# Peripherals.net
KiCad netlist of a schematic drawn in Altium Designer
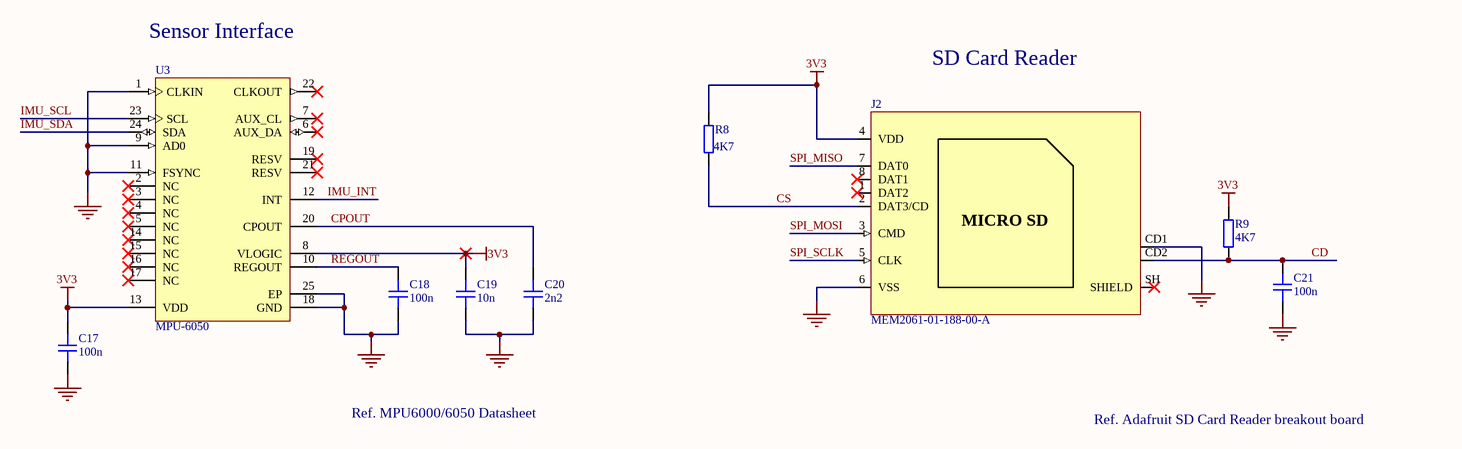
[diagram p0: Peripherals.SchDoc]

(export (version "E")
  (design (tool "Eeschema 10.0.6"))
  (components
    (comp (ref "C17")
      (value "100n")
      (footprint "CAP_0402")
      (description "Capacitor SMD 0402")
      (libsource (lib "Schematic-Lib-PhilsLab") (part "CAP_0402"))
    )
    (comp (ref "C18")
      (value "100n")
      (footprint "CAP_0402")
      (description "Capacitor SMD 0402")
      (libsource (lib "Schematic-Lib-PhilsLab") (part "CAP_0402"))
    )
    (comp (ref "C19")
      (value "10n")
      (footprint "CAP_0402")
      (description "Capacitor SMD 0402")
      (libsource (lib "Schematic-Lib-PhilsLab") (part "CAP_0402"))
    )
    (comp (ref "C20")
      (value "2n2")
      (footprint "CAP_0402")
      (description "Capacitor SMD 0402")
      (libsource (lib "Schematic-Lib-PhilsLab") (part "CAP_0402"))
    )
    (comp (ref "C21")
      (value "100n")
      (footprint "CAP_0402")
      (description "Capacitor SMD 0402")
      (libsource (lib "Schematic-Lib-PhilsLab") (part "CAP_0402"))
    )
    (comp (ref "J2")
      (value "MEM2061-01-188-00-A")
      (footprint "MEM2061-01-188-00-A")
      (description "Micro SD Card Holder Push-Push SMD")
      (fields (field (name "MANUFACTURER") "GCT"))
      (libsource (lib "Schematic-Lib-PhilsLab") (part "MEM2061-01-188-00-A"))
    )
    (comp (ref "R8")
      (value "4K7")
      (footprint "RES_0402")
      (description "Resistor SMD 0402")
      (libsource (lib "Schematic-Lib-PhilsLab") (part "RES_0402"))
    )
    (comp (ref "R9")
      (value "4K7")
      (footprint "RES_0402")
      (description "Resistor SMD 0402")
      (libsource (lib "Schematic-Lib-PhilsLab") (part "RES_0402"))
    )
    (comp (ref "U3")
      (value "MPU-6050")
      (footprint "IS-QFN-24_V")
      (fields (field (name "MANUFACTURER") "InvenSense"))
      (libsource (lib "Altium Content Vault") (part "IS-MPU-6050-QFN-24"))
    )
  )
  (nets
    (net (code "1") (name "/CD") (class "Default")
      (node (ref "C21") (pin "2") (pinfunction "2_2") (pintype "passive"))
      (node (ref "J2") (pin "CD2") (pinfunction "CARD_DETECT_CD2") (pintype "passive"))
      (node (ref "R9") (pin "1") (pinfunction "1_1") (pintype "passive"))
    )
    (net (code "2") (name "/CPOUT") (class "Default")
      (node (ref "C20") (pin "2") (pinfunction "2_2") (pintype "passive"))
      (node (ref "U3") (pin "20") (pinfunction "CPOUT_20") (pintype "passive"))
    )
    (net (code "3") (name "/CS") (class "Default")
      (node (ref "J2") (pin "2") (pinfunction "DAT3/CD_2") (pintype "bidirectional"))
      (node (ref "R8") (pin "1") (pinfunction "1_1") (pintype "passive"))
    )
    (net (code "4") (name "/IMU_INT") (class "Default")
      (node (ref "U3") (pin "12") (pinfunction "INT_12") (pintype "open_collector"))
    )
    (net (code "5") (name "/IMU_SCL") (class "Default")
      (node (ref "U3") (pin "23") (pinfunction "SCL_23") (pintype "input"))
    )
    (net (code "6") (name "/IMU_SDA") (class "Default")
      (node (ref "U3") (pin "24") (pinfunction "SDA_24") (pintype "bidirectional"))
    )
    (net (code "7") (name "/REGOUT") (class "Default")
      (node (ref "C18") (pin "2") (pinfunction "2_2") (pintype "passive"))
      (node (ref "U3") (pin "10") (pinfunction "REGOUT_10") (pintype "passive"))
    )
    (net (code "8") (name "/SPI_MISO") (class "Default")
      (node (ref "J2") (pin "7") (pinfunction "DAT0_7") (pintype "bidirectional"))
    )
    (net (code "9") (name "/SPI_MOSI") (class "Default")
      (node (ref "J2") (pin "3") (pinfunction "CMD_3") (pintype "input"))
    )
    (net (code "10") (name "/SPI_SCLK") (class "Default")
      (node (ref "J2") (pin "5") (pinfunction "CLK_5") (pintype "input"))
    )
    (net (code "11") (name "3V3") (class "Default")
      (node (ref "C17") (pin "2") (pinfunction "2_2") (pintype "passive"))
      (node (ref "C19") (pin "2") (pinfunction "2_2") (pintype "passive"))
      (node (ref "J2") (pin "4") (pinfunction "VDD_4") (pintype "power_in"))
      (node (ref "R8") (pin "2") (pinfunction "2_2") (pintype "passive"))
      (node (ref "R9") (pin "2") (pinfunction "2_2") (pintype "passive"))
      (node (ref "U3") (pin "13") (pinfunction "VDD_13") (pintype "power_in"))
      (node (ref "U3") (pin "8") (pinfunction "VLOGIC_8") (pintype "power_in"))
    )
    (net (code "12") (name "GND") (class "Default")
      (node (ref "C17") (pin "1") (pinfunction "1_1") (pintype "passive"))
      (node (ref "C18") (pin "1") (pinfunction "1_1") (pintype "passive"))
      (node (ref "C19") (pin "1") (pinfunction "1_1") (pintype "passive"))
      (node (ref "C20") (pin "1") (pinfunction "1_1") (pintype "passive"))
      (node (ref "C21") (pin "1") (pinfunction "1_1") (pintype "passive"))
      (node (ref "J2") (pin "6") (pinfunction "VSS_6") (pintype "power_in"))
      (node (ref "J2") (pin "CD1") (pinfunction "CARD_DETECT_CD1") (pintype "passive"))
      (node (ref "U3") (pin "1") (pinfunction "CLKIN_1") (pintype "input"))
      (node (ref "U3") (pin "11") (pinfunction "FSYNC_11") (pintype "input"))
      (node (ref "U3") (pin "18") (pinfunction "GND_18") (pintype "power_in"))
      (node (ref "U3") (pin "25") (pinfunction "EP_25") (pintype "power_in"))
      (node (ref "U3") (pin "9") (pinfunction "AD0_9") (pintype "input"))
    )
    (net (code "13") (name "unconnected-(J2-DAT1-Pad8)") (class "Default")
      (node (ref "J2") (pin "8") (pinfunction "DAT1_8") (pintype "bidirectional+no_connect"))
    )
    (net (code "14") (name "unconnected-(J2-DAT2-Pad1)") (class "Default")
      (node (ref "J2") (pin "1") (pinfunction "DAT2_1") (pintype "bidirectional+no_connect"))
    )
    (net (code "15") (name "unconnected-(J2-SHIELD-PadSH)") (class "Default")
      (node (ref "J2") (pin "SH") (pinfunction "SHIELD_SH") (pintype "passive+no_connect"))
    )
    (net (code "16") (name "unconnected-(U3-AUX_CL-Pad7)") (class "Default")
      (node (ref "U3") (pin "7") (pinfunction "AUX_CL_7") (pintype "output+no_connect"))
    )
    (net (code "17") (name "unconnected-(U3-AUX_DA-Pad6)") (class "Default")
      (node (ref "U3") (pin "6") (pinfunction "AUX_DA_6") (pintype "bidirectional+no_connect"))
    )
    (net (code "18") (name "unconnected-(U3-CLKOUT-Pad22)") (class "Default")
      (node (ref "U3") (pin "22") (pinfunction "CLKOUT_22") (pintype "output+no_connect"))
    )
    (net (code "19") (name "unconnected-(U3-NC-Pad2)") (class "Default")
      (node (ref "U3") (pin "2") (pinfunction "NC_2") (pintype "passive+no_connect"))
    )
    (net (code "20") (name "unconnected-(U3-NC-Pad3)") (class "Default")
      (node (ref "U3") (pin "3") (pinfunction "NC_3") (pintype "passive+no_connect"))
    )
    (net (code "21") (name "unconnected-(U3-NC-Pad4)") (class "Default")
      (node (ref "U3") (pin "4") (pinfunction "NC_4") (pintype "passive+no_connect"))
    )
    (net (code "22") (name "unconnected-(U3-NC-Pad5)") (class "Default")
      (node (ref "U3") (pin "5") (pinfunction "NC_5") (pintype "passive+no_connect"))
    )
    (net (code "23") (name "unconnected-(U3-NC-Pad14)") (class "Default")
      (node (ref "U3") (pin "14") (pinfunction "NC_14") (pintype "passive+no_connect"))
    )
    (net (code "24") (name "unconnected-(U3-NC-Pad15)") (class "Default")
      (node (ref "U3") (pin "15") (pinfunction "NC_15") (pintype "passive+no_connect"))
    )
    (net (code "25") (name "unconnected-(U3-NC-Pad16)") (class "Default")
      (node (ref "U3") (pin "16") (pinfunction "NC_16") (pintype "passive+no_connect"))
    )
    (net (code "26") (name "unconnected-(U3-NC-Pad17)") (class "Default")
      (node (ref "U3") (pin "17") (pinfunction "NC_17") (pintype "passive+no_connect"))
    )
    (net (code "27") (name "unconnected-(U3-RESV-Pad19)") (class "Default")
      (node (ref "U3") (pin "19") (pinfunction "RESV_19") (pintype "passive+no_connect"))
    )
    (net (code "28") (name "unconnected-(U3-RESV-Pad21)") (class "Default")
      (node (ref "U3") (pin "21") (pinfunction "RESV_21") (pintype "passive+no_connect"))
    )
  )
)
